# Backplane_Board.net
KiCad netlist of a schematic drawn in Altium Designer
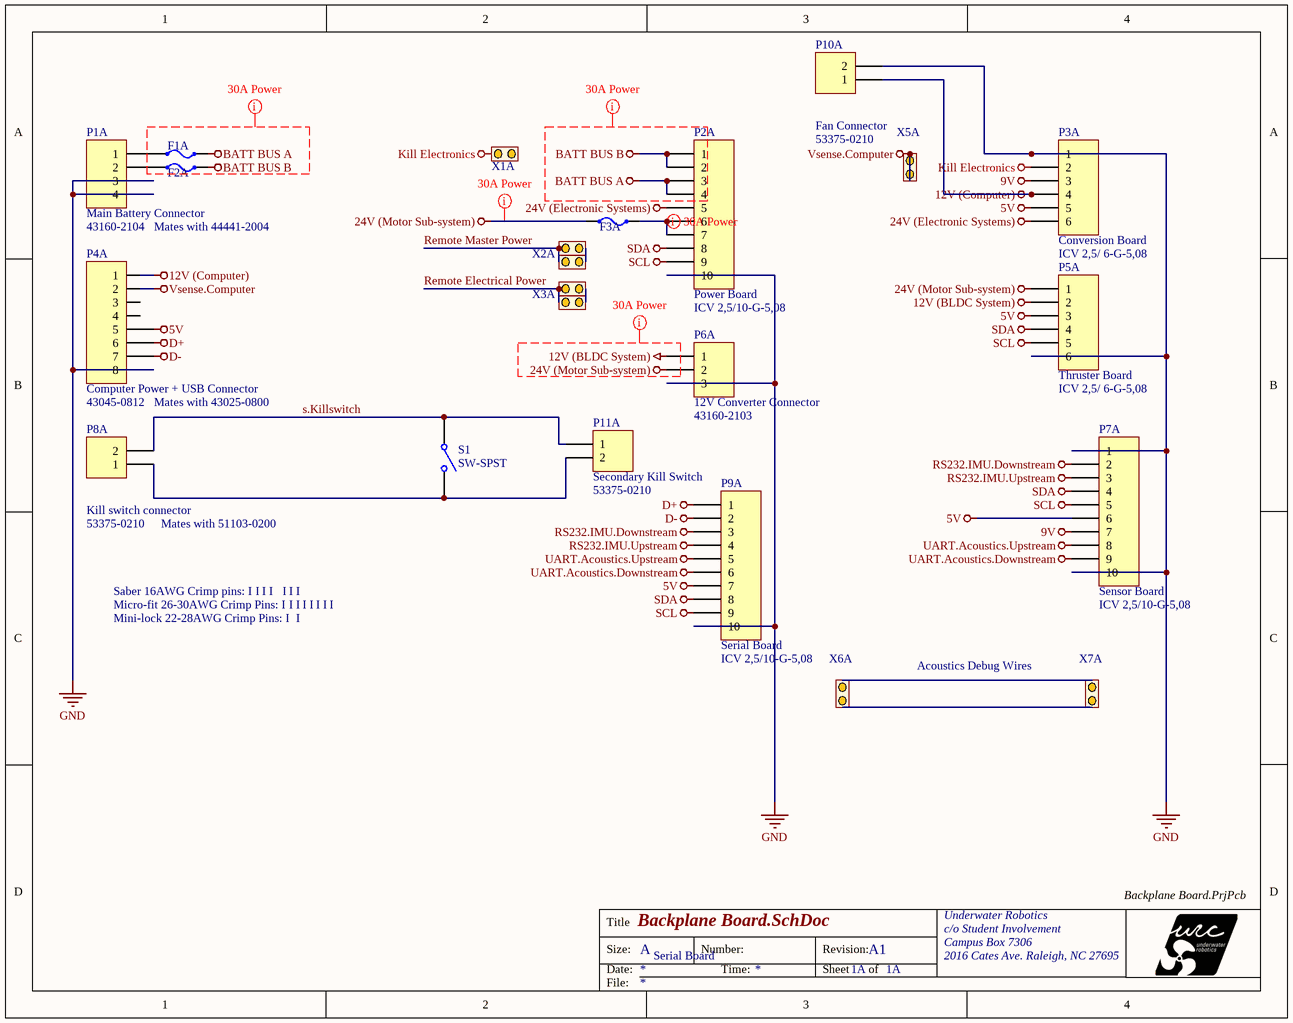
[diagram p0: Backplane Board.SchDoc]

(export (version "E")
  (design (tool "Eeschema 10.0.6"))
  (components
    (comp (ref "F1A")
      (value "3588")
      (footprint "Protected Fuse Clip")
      (description "Fuse Holder Assembly")
      (libsource (lib "Keystone SchLib") (part "3588"))
    )
    (comp (ref "F2A")
      (value "3588")
      (footprint "Protected Fuse Clip")
      (description "Fuse Holder Assembly")
      (libsource (lib "Keystone SchLib") (part "3588"))
    )
    (comp (ref "F3A")
      (value "3588")
      (footprint "Protected Fuse Clip")
      (description "Fuse Holder Assembly")
      (libsource (lib "Keystone SchLib") (part "3588"))
    )
    (comp (ref "i1A")
      (value "Saber Connector, 4pin, 44441-2004 (Placeholder)")
      (description "Saber connector, plug, 4 pin")
      (fields (field (name "MANUFACTURER PART NUMBER") "44441-2004"))
      (libsource (lib "Molex SchLib") (part "Saber Connector, 4pin, 44441-2004 (Placeholder)"))
    )
    (comp (ref "i2A")
      (value "Micro-Fit Plug8 (placeholder), 43025-0800")
      (description "8pin micro-fit connector, 43025-0800")
      (fields (field (name "MANUFACTURER PART NUMBER") "43025-0800"))
      (libsource (lib "Molex SchLib") (part "Micro-Fit Plug8 (placeholder), 43025-0800"))
    )
    (comp (ref "i3A")
      (value "General Plug2 (Placeholder), 51103-0200")
      (description "Molex Wire2PCB connector, 2pin")
      (fields (field (name "MANUFACTURER PART NUMBER") "51103-0200"))
      (libsource (lib "Molex SchLib") (part "General Plug2 (Placeholder), 51103-0200"))
    )
    (comp (ref "i4A")
      (value "Saber 16AWG Crimp Pin")
      (fields (field (name "MANUFACTURER PART NUMBER") "43375-0001"))
      (libsource (lib "") (part "Saber 16AWG Crimp Pin_1"))
    )
    (comp (ref "i5A")
      (value "Saber 16AWG Crimp Pin")
      (fields (field (name "MANUFACTURER PART NUMBER") "43375-0001"))
      (libsource (lib "Molex SchLib") (part "Saber 16AWG Crimp Pin"))
    )
    (comp (ref "i6A")
      (value "Saber 16AWG Crimp Pin")
      (fields (field (name "MANUFACTURER PART NUMBER") "43375-0001"))
      (libsource (lib "Molex SchLib") (part "Saber 16AWG Crimp Pin"))
    )
    (comp (ref "i7A")
      (value "Saber 16AWG Crimp Pin")
      (fields (field (name "MANUFACTURER PART NUMBER") "43375-0001"))
      (libsource (lib "Molex SchLib") (part "Saber 16AWG Crimp Pin"))
    )
    (comp (ref "i8A")
      (value "Saber 16AWG Crimp Pin")
      (fields (field (name "MANUFACTURER PART NUMBER") "43375-0001"))
      (libsource (lib "Molex SchLib") (part "Saber 16AWG Crimp Pin"))
    )
    (comp (ref "i9A")
      (value "Saber 16AWG Crimp Pin")
      (fields (field (name "MANUFACTURER PART NUMBER") "43375-0001"))
      (libsource (lib "Molex SchLib") (part "Saber 16AWG Crimp Pin"))
    )
    (comp (ref "i10A")
      (value "Saber 16AWG Crimp Pin")
      (fields (field (name "MANUFACTURER PART NUMBER") "43375-0001"))
      (libsource (lib "Molex SchLib") (part "Saber 16AWG Crimp Pin"))
    )
    (comp (ref "i11A")
      (value "Micro-fit 26-30AWG Crimp pin (Placeholder)")
      (description "Standard Crimp pin for Micro-fit series")
      (fields (field (name "MANUFACTURER PART NUMBER") "43030-0005"))
      (libsource (lib "") (part "Micro-fit 26-30AWG Crimp pin (Placeholder)_1"))
    )
    (comp (ref "i12A")
      (value "Micro-fit 26-30AWG Crimp pin (Placeholder)")
      (description "Standard Crimp pin for Micro-fit series")
      (fields (field (name "MANUFACTURER PART NUMBER") "43030-0005"))
      (libsource (lib "Molex SchLib") (part "Micro-fit 26-30AWG Crimp pin (Placeholder)"))
    )
    (comp (ref "i13A")
      (value "Micro-fit 26-30AWG Crimp pin (Placeholder)")
      (description "Standard Crimp pin for Micro-fit series")
      (fields (field (name "MANUFACTURER PART NUMBER") "43030-0005"))
      (libsource (lib "Molex SchLib") (part "Micro-fit 26-30AWG Crimp pin (Placeholder)"))
    )
    (comp (ref "i14A")
      (value "Micro-fit 26-30AWG Crimp pin (Placeholder)")
      (description "Standard Crimp pin for Micro-fit series")
      (fields (field (name "MANUFACTURER PART NUMBER") "43030-0005"))
      (libsource (lib "Molex SchLib") (part "Micro-fit 26-30AWG Crimp pin (Placeholder)"))
    )
    (comp (ref "i15A")
      (value "Micro-fit 26-30AWG Crimp pin (Placeholder)")
      (description "Standard Crimp pin for Micro-fit series")
      (fields (field (name "MANUFACTURER PART NUMBER") "43030-0005"))
      (libsource (lib "Molex SchLib") (part "Micro-fit 26-30AWG Crimp pin (Placeholder)"))
    )
    (comp (ref "i16A")
      (value "Micro-fit 26-30AWG Crimp pin (Placeholder)")
      (description "Standard Crimp pin for Micro-fit series")
      (fields (field (name "MANUFACTURER PART NUMBER") "43030-0005"))
      (libsource (lib "Molex SchLib") (part "Micro-fit 26-30AWG Crimp pin (Placeholder)"))
    )
    (comp (ref "i17A")
      (value "Micro-fit 26-30AWG Crimp pin (Placeholder)")
      (description "Standard Crimp pin for Micro-fit series")
      (fields (field (name "MANUFACTURER PART NUMBER") "43030-0005"))
      (libsource (lib "Molex SchLib") (part "Micro-fit 26-30AWG Crimp pin (Placeholder)"))
    )
    (comp (ref "i18A")
      (value "Micro-fit 26-30AWG Crimp pin (Placeholder)")
      (description "Standard Crimp pin for Micro-fit series")
      (fields (field (name "MANUFACTURER PART NUMBER") "43030-0005"))
      (libsource (lib "Molex SchLib") (part "Micro-fit 26-30AWG Crimp pin (Placeholder)"))
    )
    (comp (ref "i19A")
      (value "Mini-lock 22-28AWG (Placeholder), 50351-8000")
      (description "Standard Crimp pin for Mini-lock series")
      (fields (field (name "MANUFACTURER PART NUMBER") "50351-8000"))
      (libsource (lib "Molex SchLib") (part "Mini-lock 22-28AWG (Placeholder), 50351-8000"))
    )
    (comp (ref "i20A")
      (value "Mini-lock 22-28AWG (Placeholder), 50351-8000")
      (description "Standard Crimp pin for Mini-lock series")
      (fields (field (name "MANUFACTURER PART NUMBER") "50351-8000"))
      (libsource (lib "") (part "Mini-lock 22-28AWG (Placeholder), 50351-8000_1"))
    )
    (comp (ref "P1A")
      (value "Main Battery Connector")
      (footprint "431602104 Header w/ Plug")
      (fields (field (name "MANUFACTURER PART NUMBER") "43160-2104"))
      (libsource (lib "Molex SchLib") (part "Molex Header 4, 43160-2104"))
    )
    (comp (ref "P2A")
      (value "Power Board")
      (footprint "ICV 2,5/10-G-5,08")
      (description "Header, 10-Pin")
      (fields (field (name "MANUFACTURER PART NUMBER") "ICV 2,5/10-G-5,08"))
      (libsource (lib "Pheonix Connectors") (part "ICV 2,5/10-G-5,08"))
    )
    (comp (ref "P3A")
      (value "Conversion Board")
      (footprint "ICV 2,5/ 6-G-5,08")
      (description "Header, 6-Pin")
      (fields (field (name "MANUFACTURER PART NUMBER") "ICV 2,5/ 6-G-5,08"))
      (libsource (lib "Pheonix Connectors") (part "ICV 2,5/ 6-G-5,08"))
    )
    (comp (ref "P4A")
      (value "Computer Power + USB Connector")
      (footprint "43045-0812 Microfit Header w/ plug")
      (fields (field (name "MANUFACTURER PART NUMBER") "43045-0812"))
      (libsource (lib "Molex SchLib") (part "Molex Header 8, 43045-0812"))
    )
    (comp (ref "P5A")
      (value "Thruster Board")
      (footprint "ICV 2,5/ 6-G-5,08")
      (description "Header, 6-Pin")
      (fields (field (name "MANUFACTURER PART NUMBER") "ICV 2,5/ 6-G-5,08"))
      (libsource (lib "Pheonix Connectors") (part "ICV 2,5/ 6-G-5,08"))
    )
    (comp (ref "P6A")
      (value "12V Converter Connector")
      (footprint "431602103 Header w/ Plug")
      (fields (field (name "MANUFACTURER PART NUMBER") "43160-2103"))
      (libsource (lib "Molex SchLib") (part "Molex Header, 431602103"))
    )
    (comp (ref "P7A")
      (value "Sensor Board")
      (footprint "ICV 2,5/10-G-5,08")
      (description "Header, 10-Pin")
      (fields (field (name "MANUFACTURER PART NUMBER") "ICV 2,5/10-G-5,08"))
      (libsource (lib "Pheonix Contact") (part "ICV 2,5/10-G-5,08"))
    )
    (comp (ref "P8A")
      (value "Kill switch connector")
      (footprint "533750210 header w/ plug")
      (fields (field (name "MANUFACTURER PART NUMBER") "53375-0210"))
      (libsource (lib "Molex SchLib") (part "Molex Header 2,  53375-0210"))
    )
    (comp (ref "P9A")
      (value "Serial Board")
      (footprint "ICV 2,5/10-G-5,08")
      (description "Header, 10-Pin")
      (fields (field (name "MANUFACTURER PART NUMBER") "ICV 2,5/10-G-5,08"))
      (libsource (lib "Pheonix Contact") (part "ICV 2,5/10-G-5,08"))
    )
    (comp (ref "P10A")
      (value "Fan Connector")
      (footprint "533750210 header w/ plug")
      (fields (field (name "MANUFACTURER PART NUMBER") "53375-0210"))
      (libsource (lib "Molex SchLib") (part "Molex Header 2,  53375-0210"))
    )
    (comp (ref "P11A")
      (value "Secondary Kill Switch")
      (footprint "533750210 header w/ plug")
      (fields (field (name "MANUFACTURER PART NUMBER") "53375-0210"))
      (libsource (lib "") (part "Molex Header 2,  53375-0210_1"))
    )
    (comp (ref "S1")
      (value "SW-SPST")
      (footprint "SPST-2")
      (description "Single-Pole, Single-Throw Switch")
      (fields (field (name "PUBLISHER") "Altium Limited"))
      (libsource (lib "Miscellaneous Devices") (part "SW-SPST"))
    )
    (comp (ref "X1A")
      (value "Header")
      (footprint "1x2 Header")
      (description "1x2 Header")
      (libsource (lib "") (part "1x2 Header_1"))
    )
    (comp (ref "X2A")
      (value "Header")
      (footprint "2x2 Header w/ division")
      (description "2x2 Header")
      (libsource (lib "URC") (part "2x2 Header"))
    )
    (comp (ref "X3A")
      (value "Header")
      (footprint "2x2 Header w/ division")
      (description "2x2 Header")
      (libsource (lib "URC") (part "2x2 Header"))
    )
    (comp (ref "X5A")
      (value "Header")
      (footprint "1x2 Header")
      (description "1x2 Header")
      (libsource (lib "URC_Lib") (part "1x2 Header"))
    )
    (comp (ref "X6A")
      (value "Header")
      (footprint "1x2 Header")
      (description "1x2 Header")
      (libsource (lib "URC_Lib") (part "1x2 Header"))
    )
    (comp (ref "X7A")
      (value "Header")
      (footprint "1x2 Header")
      (description "1x2 Header")
      (libsource (lib "URC_Lib") (part "1x2 Header"))
    )
  )
  (nets
    (net (code "1") (name "/Remote Electrical Power") (class "Default")
      (node (ref "X3A") (pin "1") (pinfunction "1_1") (pintype "passive"))
      (node (ref "X3A") (pin "3") (pinfunction "3_3") (pintype "passive"))
    )
    (net (code "2") (name "/Remote Master Power") (class "Default")
      (node (ref "X2A") (pin "1") (pinfunction "1_1") (pintype "passive"))
      (node (ref "X2A") (pin "3") (pinfunction "3_3") (pintype "passive"))
    )
    (net (code "3") (name "/s.Killswitch") (class "Default")
      (node (ref "P11A") (pin "1") (pinfunction "1_1") (pintype "passive"))
      (node (ref "P8A") (pin "2") (pinfunction "2_2") (pintype "passive"))
      (node (ref "S1") (pin "1") (pinfunction "COMMON_1") (pintype "passive"))
    )
    (net (code "4") (name "5V") (class "Default")
      (node (ref "P3A") (pin "5") (pinfunction "5_5") (pintype "passive"))
      (node (ref "P4A") (pin "5") (pinfunction "5_5") (pintype "passive"))
      (node (ref "P5A") (pin "3") (pinfunction "3_3") (pintype "passive"))
      (node (ref "P7A") (pin "6") (pinfunction "6_6") (pintype "passive"))
      (node (ref "P9A") (pin "7") (pinfunction "7_7") (pintype "passive"))
    )
    (net (code "5") (name "9V") (class "Default")
      (node (ref "P3A") (pin "3") (pinfunction "3_3") (pintype "passive"))
      (node (ref "P7A") (pin "7") (pinfunction "7_7") (pintype "passive"))
    )
    (net (code "6") (name "12V (BLDC System)") (class "Default")
      (node (ref "P5A") (pin "2") (pinfunction "2_2") (pintype "passive"))
      (node (ref "P6A") (pin "1") (pinfunction "1_1") (pintype "passive"))
    )
    (net (code "7") (name "12V (Computer)") (class "Default")
      (node (ref "P10A") (pin "1") (pinfunction "1_1") (pintype "passive"))
      (node (ref "P3A") (pin "4") (pinfunction "4_4") (pintype "passive"))
      (node (ref "P4A") (pin "1") (pinfunction "1_1") (pintype "passive"))
    )
    (net (code "8") (name "24V (Electronic Systems)") (class "Default")
      (node (ref "P2A") (pin "5") (pinfunction "5_5") (pintype "passive"))
      (node (ref "P3A") (pin "6") (pinfunction "6_6") (pintype "passive"))
    )
    (net (code "9") (name "24V (Motor Sub-system)") (class "Default")
      (node (ref "F3A") (pin "2") (pinfunction "2_2") (pintype "passive"))
      (node (ref "P5A") (pin "1") (pinfunction "1_1") (pintype "passive"))
      (node (ref "P6A") (pin "2") (pinfunction "2_2") (pintype "passive"))
    )
    (net (code "10") (name "BATT BUS A") (class "Default")
      (node (ref "F1A") (pin "1") (pinfunction "1_1") (pintype "passive"))
      (node (ref "P2A") (pin "3") (pinfunction "3_3") (pintype "passive"))
      (node (ref "P2A") (pin "4") (pinfunction "4_4") (pintype "passive"))
    )
    (net (code "11") (name "BATT BUS B") (class "Default")
      (node (ref "F2A") (pin "1") (pinfunction "1_1") (pintype "passive"))
      (node (ref "P2A") (pin "1") (pinfunction "1_1") (pintype "passive"))
      (node (ref "P2A") (pin "2") (pinfunction "2_2") (pintype "passive"))
    )
    (net (code "12") (name "D+") (class "Default")
      (node (ref "P4A") (pin "6") (pinfunction "6_6") (pintype "passive"))
      (node (ref "P9A") (pin "1") (pinfunction "1_1") (pintype "passive"))
    )
    (net (code "13") (name "D-") (class "Default")
      (node (ref "P4A") (pin "7") (pinfunction "7_7") (pintype "passive"))
      (node (ref "P9A") (pin "2") (pinfunction "2_2") (pintype "passive"))
    )
    (net (code "14") (name "GND") (class "Default")
      (node (ref "P10A") (pin "2") (pinfunction "2_2") (pintype "passive"))
      (node (ref "P1A") (pin "3") (pinfunction "3_3") (pintype "passive"))
      (node (ref "P1A") (pin "4") (pinfunction "4_4") (pintype "passive"))
      (node (ref "P2A") (pin "10") (pinfunction "10_10") (pintype "passive"))
      (node (ref "P3A") (pin "1") (pinfunction "1_1") (pintype "passive"))
      (node (ref "P4A") (pin "8") (pinfunction "8_8") (pintype "passive"))
      (node (ref "P5A") (pin "6") (pinfunction "6_6") (pintype "passive"))
      (node (ref "P6A") (pin "3") (pinfunction "3_3") (pintype "passive"))
      (node (ref "P7A") (pin "1") (pinfunction "1_1") (pintype "passive"))
      (node (ref "P7A") (pin "10") (pinfunction "10_10") (pintype "passive"))
      (node (ref "P9A") (pin "10") (pinfunction "10_10") (pintype "passive"))
    )
    (net (code "15") (name "Kill Electronics") (class "Default")
      (node (ref "P3A") (pin "2") (pinfunction "2_2") (pintype "passive"))
      (node (ref "X1A") (pin "1") (pinfunction "1_1") (pintype "passive"))
    )
    (net (code "16") (name "Net-(F1A-Pad2)") (class "Default")
      (node (ref "F1A") (pin "2") (pinfunction "2_2") (pintype "passive"))
      (node (ref "P1A") (pin "1") (pinfunction "1_1") (pintype "passive"))
    )
    (net (code "17") (name "Net-(F2A-Pad2)") (class "Default")
      (node (ref "F2A") (pin "2") (pinfunction "2_2") (pintype "passive"))
      (node (ref "P1A") (pin "2") (pinfunction "2_2") (pintype "passive"))
    )
    (net (code "18") (name "Net-(F3A-Pad1)") (class "Default")
      (node (ref "F3A") (pin "1") (pinfunction "1_1") (pintype "passive"))
      (node (ref "P2A") (pin "6") (pinfunction "6_6") (pintype "passive"))
      (node (ref "P2A") (pin "7") (pinfunction "7_7") (pintype "passive"))
    )
    (net (code "19") (name "Net-(S1-NO)") (class "Default")
      (node (ref "P11A") (pin "2") (pinfunction "2_2") (pintype "passive"))
      (node (ref "P8A") (pin "1") (pinfunction "1_1") (pintype "passive"))
      (node (ref "S1") (pin "2") (pinfunction "NO_2") (pintype "passive"))
    )
    (net (code "20") (name "Net-(X2A-Pad2)") (class "Default")
      (node (ref "X2A") (pin "2") (pinfunction "2_2") (pintype "passive"))
      (node (ref "X2A") (pin "4") (pinfunction "4_4") (pintype "passive"))
    )
    (net (code "21") (name "Net-(X3A-Pad2)") (class "Default")
      (node (ref "X3A") (pin "2") (pinfunction "2_2") (pintype "passive"))
      (node (ref "X3A") (pin "4") (pinfunction "4_4") (pintype "passive"))
    )
    (net (code "22") (name "Net-(X6A-Pad1)") (class "Default")
      (node (ref "X6A") (pin "1") (pinfunction "1_1") (pintype "passive"))
      (node (ref "X7A") (pin "1") (pinfunction "1_1") (pintype "passive"))
    )
    (net (code "23") (name "Net-(X6A-Pad2)") (class "Default")
      (node (ref "X6A") (pin "2") (pinfunction "2_2") (pintype "passive"))
      (node (ref "X7A") (pin "2") (pinfunction "2_2") (pintype "passive"))
    )
    (net (code "24") (name "RS232.IMU.Downstream") (class "Default")
      (node (ref "P7A") (pin "2") (pinfunction "2_2") (pintype "passive"))
      (node (ref "P9A") (pin "3") (pinfunction "3_3") (pintype "passive"))
    )
    (net (code "25") (name "RS232.IMU.Upstream") (class "Default")
      (node (ref "P7A") (pin "3") (pinfunction "3_3") (pintype "passive"))
      (node (ref "P9A") (pin "4") (pinfunction "4_4") (pintype "passive"))
    )
    (net (code "26") (name "SCL") (class "Default")
      (node (ref "P2A") (pin "9") (pinfunction "9_9") (pintype "passive"))
      (node (ref "P5A") (pin "5") (pinfunction "5_5") (pintype "passive"))
      (node (ref "P7A") (pin "5") (pinfunction "5_5") (pintype "passive"))
      (node (ref "P9A") (pin "9") (pinfunction "9_9") (pintype "passive"))
    )
    (net (code "27") (name "SDA") (class "Default")
      (node (ref "P2A") (pin "8") (pinfunction "8_8") (pintype "passive"))
      (node (ref "P5A") (pin "4") (pinfunction "4_4") (pintype "passive"))
      (node (ref "P7A") (pin "4") (pinfunction "4_4") (pintype "passive"))
      (node (ref "P9A") (pin "8") (pinfunction "8_8") (pintype "passive"))
    )
    (net (code "28") (name "UART.Acoustics.Downstream") (class "Default")
      (node (ref "P7A") (pin "9") (pinfunction "9_9") (pintype "passive"))
      (node (ref "P9A") (pin "6") (pinfunction "6_6") (pintype "passive"))
    )
    (net (code "29") (name "UART.Acoustics.Upstream") (class "Default")
      (node (ref "P7A") (pin "8") (pinfunction "8_8") (pintype "passive"))
      (node (ref "P9A") (pin "5") (pinfunction "5_5") (pintype "passive"))
    )
    (net (code "30") (name "Vsense.Computer") (class "Default")
      (node (ref "P4A") (pin "2") (pinfunction "2_2") (pintype "passive"))
      (node (ref "X5A") (pin "1") (pinfunction "1_1") (pintype "passive"))
      (node (ref "X5A") (pin "2") (pinfunction "2_2") (pintype "passive"))
    )
    (net (code "31") (name "unconnected-(P4A-Pad3)") (class "Default")
      (node (ref "P4A") (pin "3") (pinfunction "3_3") (pintype "passive"))
    )
    (net (code "32") (name "unconnected-(P4A-Pad4)") (class "Default")
      (node (ref "P4A") (pin "4") (pinfunction "4_4") (pintype "passive"))
    )
    (net (code "33") (name "unconnected-(X1A-Pad2)") (class "Default")
      (node (ref "X1A") (pin "2") (pinfunction "2_2") (pintype "passive"))
    )
  )
)
